# ADA_1_1.net
KiCad netlist of a schematic drawn in EAGLE
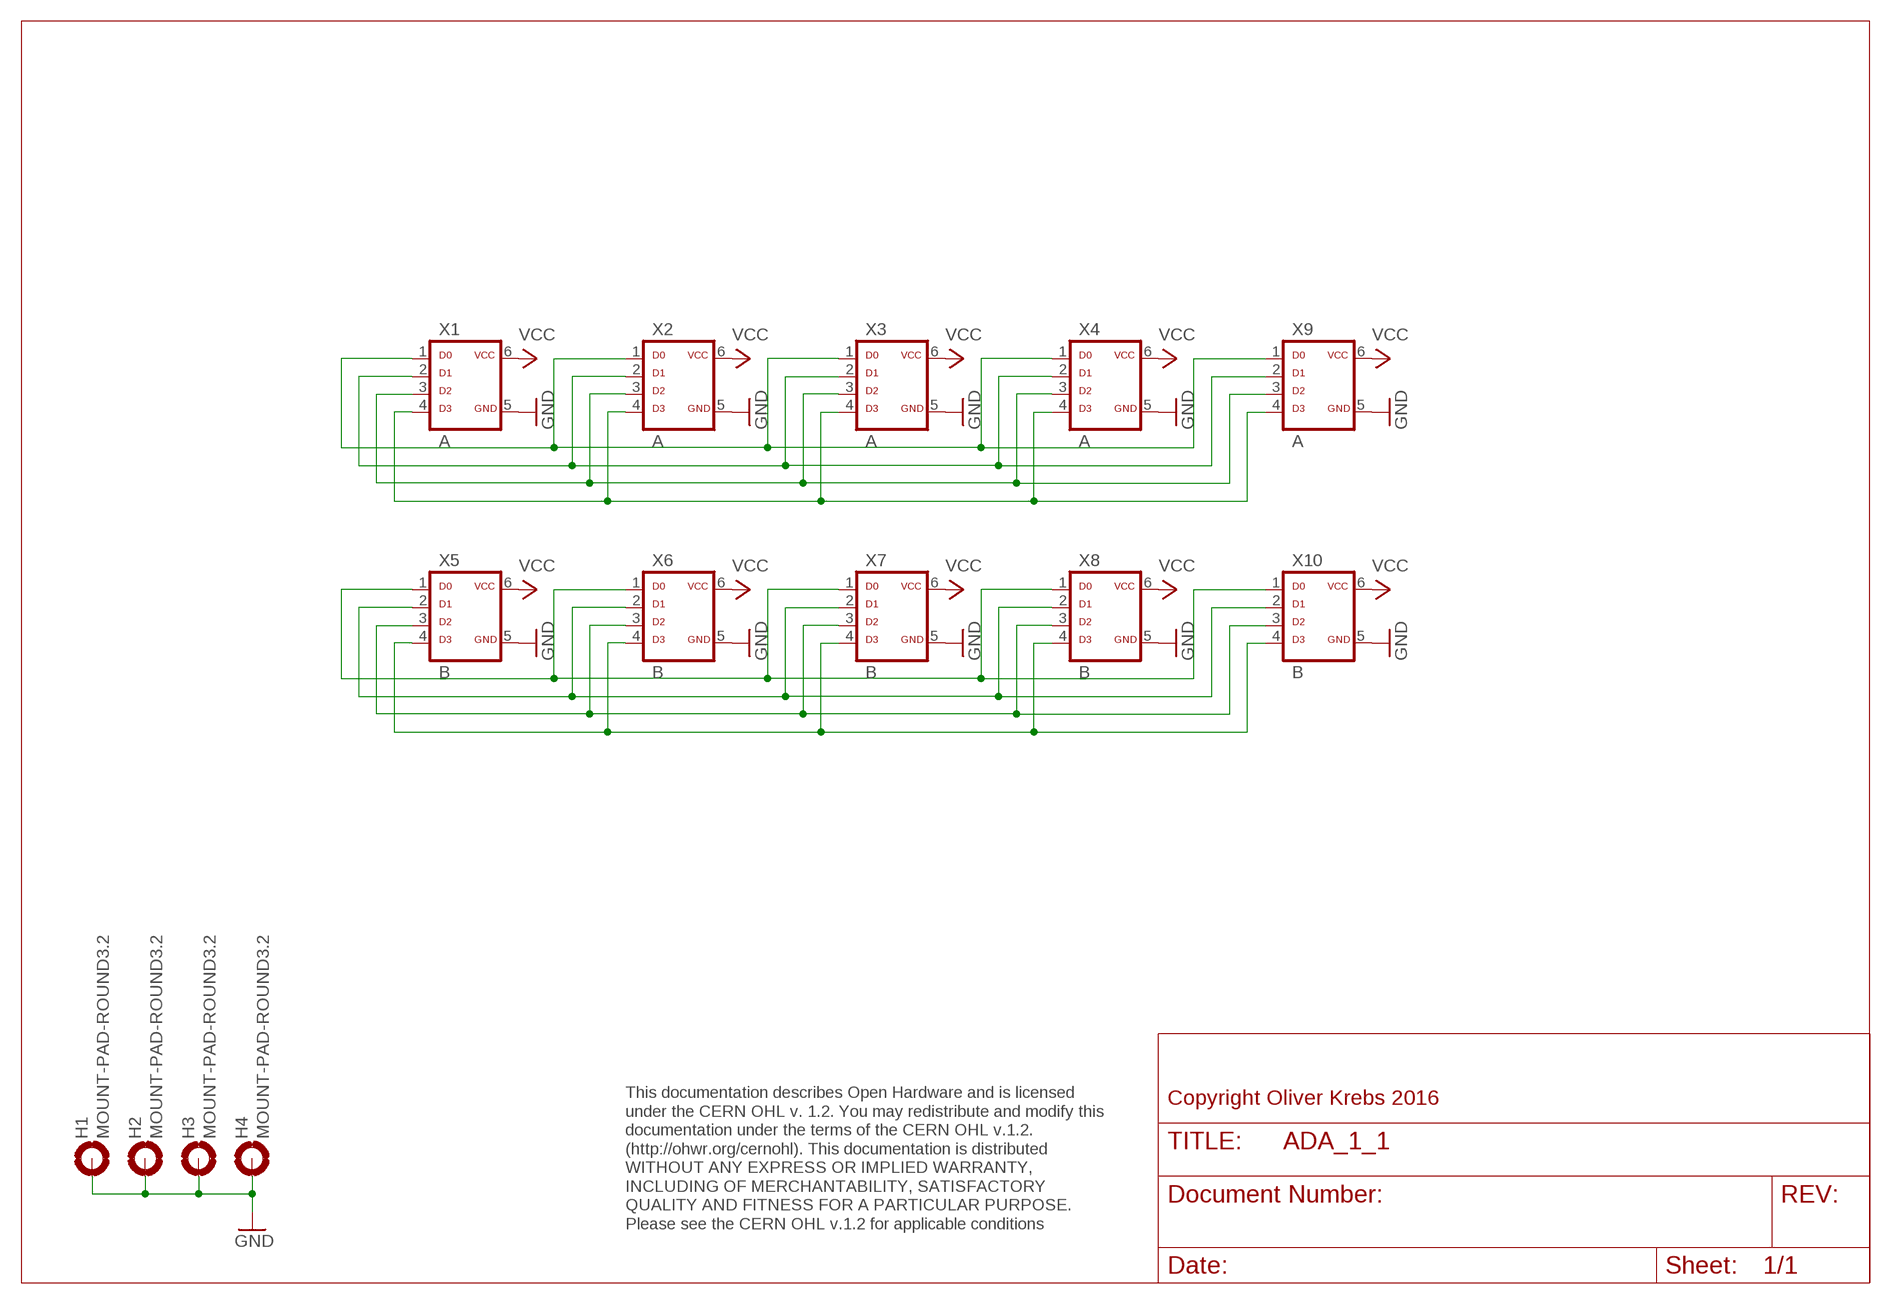
[diagram p0: schematic, sheet 1]

(export (version "E")
  (design (tool "Eeschema 10.0.6"))
  (components
    (comp (ref "H1")
      (value "MOUNT-PAD-ROUND3.2")
      (footprint "eagle-import:3,2-PAD")
      (libsource (lib "eagle-import") (part "MOUNT-PAD-ROUND3.2"))
    )
    (comp (ref "H2")
      (value "MOUNT-PAD-ROUND3.2")
      (footprint "eagle-import:3,2-PAD")
      (libsource (lib "eagle-import") (part "MOUNT-PAD-ROUND3.2"))
    )
    (comp (ref "H3")
      (value "MOUNT-PAD-ROUND3.2")
      (footprint "eagle-import:3,2-PAD")
      (libsource (lib "eagle-import") (part "MOUNT-PAD-ROUND3.2"))
    )
    (comp (ref "H4")
      (value "MOUNT-PAD-ROUND3.2")
      (footprint "eagle-import:3,2-PAD")
      (libsource (lib "eagle-import") (part "MOUNT-PAD-ROUND3.2"))
    )
    (comp (ref "X1")
      (value "A")
      (footprint "eagle-import:ML-6")
      (libsource (lib "eagle-import") (part "ML6D"))
    )
    (comp (ref "X2")
      (value "A")
      (footprint "eagle-import:ML-6")
      (libsource (lib "eagle-import") (part "ML6D"))
    )
    (comp (ref "X3")
      (value "A")
      (footprint "eagle-import:ML-6")
      (libsource (lib "eagle-import") (part "ML6D"))
    )
    (comp (ref "X4")
      (value "A")
      (footprint "eagle-import:ML-6")
      (libsource (lib "eagle-import") (part "ML6D"))
    )
    (comp (ref "X5")
      (value "B")
      (footprint "eagle-import:ML-6")
      (libsource (lib "eagle-import") (part "ML6D"))
    )
    (comp (ref "X6")
      (value "B")
      (footprint "eagle-import:ML-6")
      (libsource (lib "eagle-import") (part "ML6D"))
    )
    (comp (ref "X7")
      (value "B")
      (footprint "eagle-import:ML-6")
      (libsource (lib "eagle-import") (part "ML6D"))
    )
    (comp (ref "X8")
      (value "B")
      (footprint "eagle-import:ML-6")
      (libsource (lib "eagle-import") (part "ML6D"))
    )
    (comp (ref "X9")
      (value "A")
      (footprint "eagle-import:ML-6")
      (libsource (lib "eagle-import") (part "ML6D"))
    )
    (comp (ref "X10")
      (value "B")
      (footprint "eagle-import:ML-6")
      (libsource (lib "eagle-import") (part "ML6D"))
    )
  )
  (nets
    (net (code "1") (name "GND") (class "Default")
      (node (ref "H1") (pin "B3,2") (pinfunction "MOUNT_B3,2") (pintype "passive"))
      (node (ref "H2") (pin "B3,2") (pinfunction "MOUNT_B3,2") (pintype "passive"))
      (node (ref "H3") (pin "B3,2") (pinfunction "MOUNT_B3,2") (pintype "passive"))
      (node (ref "H4") (pin "B3,2") (pinfunction "MOUNT_B3,2") (pintype "passive"))
      (node (ref "X1") (pin "5") (pinfunction "5_5") (pintype "passive"))
      (node (ref "X10") (pin "5") (pinfunction "5_5") (pintype "passive"))
      (node (ref "X2") (pin "5") (pinfunction "5_5") (pintype "passive"))
      (node (ref "X3") (pin "5") (pinfunction "5_5") (pintype "passive"))
      (node (ref "X4") (pin "5") (pinfunction "5_5") (pintype "passive"))
      (node (ref "X5") (pin "5") (pinfunction "5_5") (pintype "passive"))
      (node (ref "X6") (pin "5") (pinfunction "5_5") (pintype "passive"))
      (node (ref "X7") (pin "5") (pinfunction "5_5") (pintype "passive"))
      (node (ref "X8") (pin "5") (pinfunction "5_5") (pintype "passive"))
      (node (ref "X9") (pin "5") (pinfunction "5_5") (pintype "passive"))
    )
    (net (code "2") (name "Net-(X1-Pad1)") (class "Default")
      (node (ref "X1") (pin "1") (pinfunction "1_1") (pintype "passive"))
      (node (ref "X2") (pin "1") (pinfunction "1_1") (pintype "passive"))
      (node (ref "X3") (pin "1") (pinfunction "1_1") (pintype "passive"))
      (node (ref "X4") (pin "1") (pinfunction "1_1") (pintype "passive"))
      (node (ref "X9") (pin "1") (pinfunction "1_1") (pintype "passive"))
    )
    (net (code "3") (name "Net-(X1-Pad2)") (class "Default")
      (node (ref "X1") (pin "2") (pinfunction "2_2") (pintype "passive"))
      (node (ref "X2") (pin "2") (pinfunction "2_2") (pintype "passive"))
      (node (ref "X3") (pin "2") (pinfunction "2_2") (pintype "passive"))
      (node (ref "X4") (pin "2") (pinfunction "2_2") (pintype "passive"))
      (node (ref "X9") (pin "2") (pinfunction "2_2") (pintype "passive"))
    )
    (net (code "4") (name "Net-(X1-Pad3)") (class "Default")
      (node (ref "X1") (pin "3") (pinfunction "3_3") (pintype "passive"))
      (node (ref "X2") (pin "3") (pinfunction "3_3") (pintype "passive"))
      (node (ref "X3") (pin "3") (pinfunction "3_3") (pintype "passive"))
      (node (ref "X4") (pin "3") (pinfunction "3_3") (pintype "passive"))
      (node (ref "X9") (pin "3") (pinfunction "3_3") (pintype "passive"))
    )
    (net (code "5") (name "Net-(X1-Pad4)") (class "Default")
      (node (ref "X1") (pin "4") (pinfunction "4_4") (pintype "passive"))
      (node (ref "X2") (pin "4") (pinfunction "4_4") (pintype "passive"))
      (node (ref "X3") (pin "4") (pinfunction "4_4") (pintype "passive"))
      (node (ref "X4") (pin "4") (pinfunction "4_4") (pintype "passive"))
      (node (ref "X9") (pin "4") (pinfunction "4_4") (pintype "passive"))
    )
    (net (code "6") (name "Net-(X10-Pad1)") (class "Default")
      (node (ref "X10") (pin "1") (pinfunction "1_1") (pintype "passive"))
      (node (ref "X5") (pin "1") (pinfunction "1_1") (pintype "passive"))
      (node (ref "X6") (pin "1") (pinfunction "1_1") (pintype "passive"))
      (node (ref "X7") (pin "1") (pinfunction "1_1") (pintype "passive"))
      (node (ref "X8") (pin "1") (pinfunction "1_1") (pintype "passive"))
    )
    (net (code "7") (name "Net-(X10-Pad2)") (class "Default")
      (node (ref "X10") (pin "2") (pinfunction "2_2") (pintype "passive"))
      (node (ref "X5") (pin "2") (pinfunction "2_2") (pintype "passive"))
      (node (ref "X6") (pin "2") (pinfunction "2_2") (pintype "passive"))
      (node (ref "X7") (pin "2") (pinfunction "2_2") (pintype "passive"))
      (node (ref "X8") (pin "2") (pinfunction "2_2") (pintype "passive"))
    )
    (net (code "8") (name "Net-(X10-Pad3)") (class "Default")
      (node (ref "X10") (pin "3") (pinfunction "3_3") (pintype "passive"))
      (node (ref "X5") (pin "3") (pinfunction "3_3") (pintype "passive"))
      (node (ref "X6") (pin "3") (pinfunction "3_3") (pintype "passive"))
      (node (ref "X7") (pin "3") (pinfunction "3_3") (pintype "passive"))
      (node (ref "X8") (pin "3") (pinfunction "3_3") (pintype "passive"))
    )
    (net (code "9") (name "Net-(X10-Pad4)") (class "Default")
      (node (ref "X10") (pin "4") (pinfunction "4_4") (pintype "passive"))
      (node (ref "X5") (pin "4") (pinfunction "4_4") (pintype "passive"))
      (node (ref "X6") (pin "4") (pinfunction "4_4") (pintype "passive"))
      (node (ref "X7") (pin "4") (pinfunction "4_4") (pintype "passive"))
      (node (ref "X8") (pin "4") (pinfunction "4_4") (pintype "passive"))
    )
    (net (code "10") (name "VCC") (class "Default")
      (node (ref "X1") (pin "6") (pinfunction "6_6") (pintype "passive"))
      (node (ref "X10") (pin "6") (pinfunction "6_6") (pintype "passive"))
      (node (ref "X2") (pin "6") (pinfunction "6_6") (pintype "passive"))
      (node (ref "X3") (pin "6") (pinfunction "6_6") (pintype "passive"))
      (node (ref "X4") (pin "6") (pinfunction "6_6") (pintype "passive"))
      (node (ref "X5") (pin "6") (pinfunction "6_6") (pintype "passive"))
      (node (ref "X6") (pin "6") (pinfunction "6_6") (pintype "passive"))
      (node (ref "X7") (pin "6") (pinfunction "6_6") (pintype "passive"))
      (node (ref "X8") (pin "6") (pinfunction "6_6") (pintype "passive"))
      (node (ref "X9") (pin "6") (pinfunction "6_6") (pintype "passive"))
    )
  )
)
